# TXmdl_1.net
KiCad netlist of a schematic drawn in Altium Designer
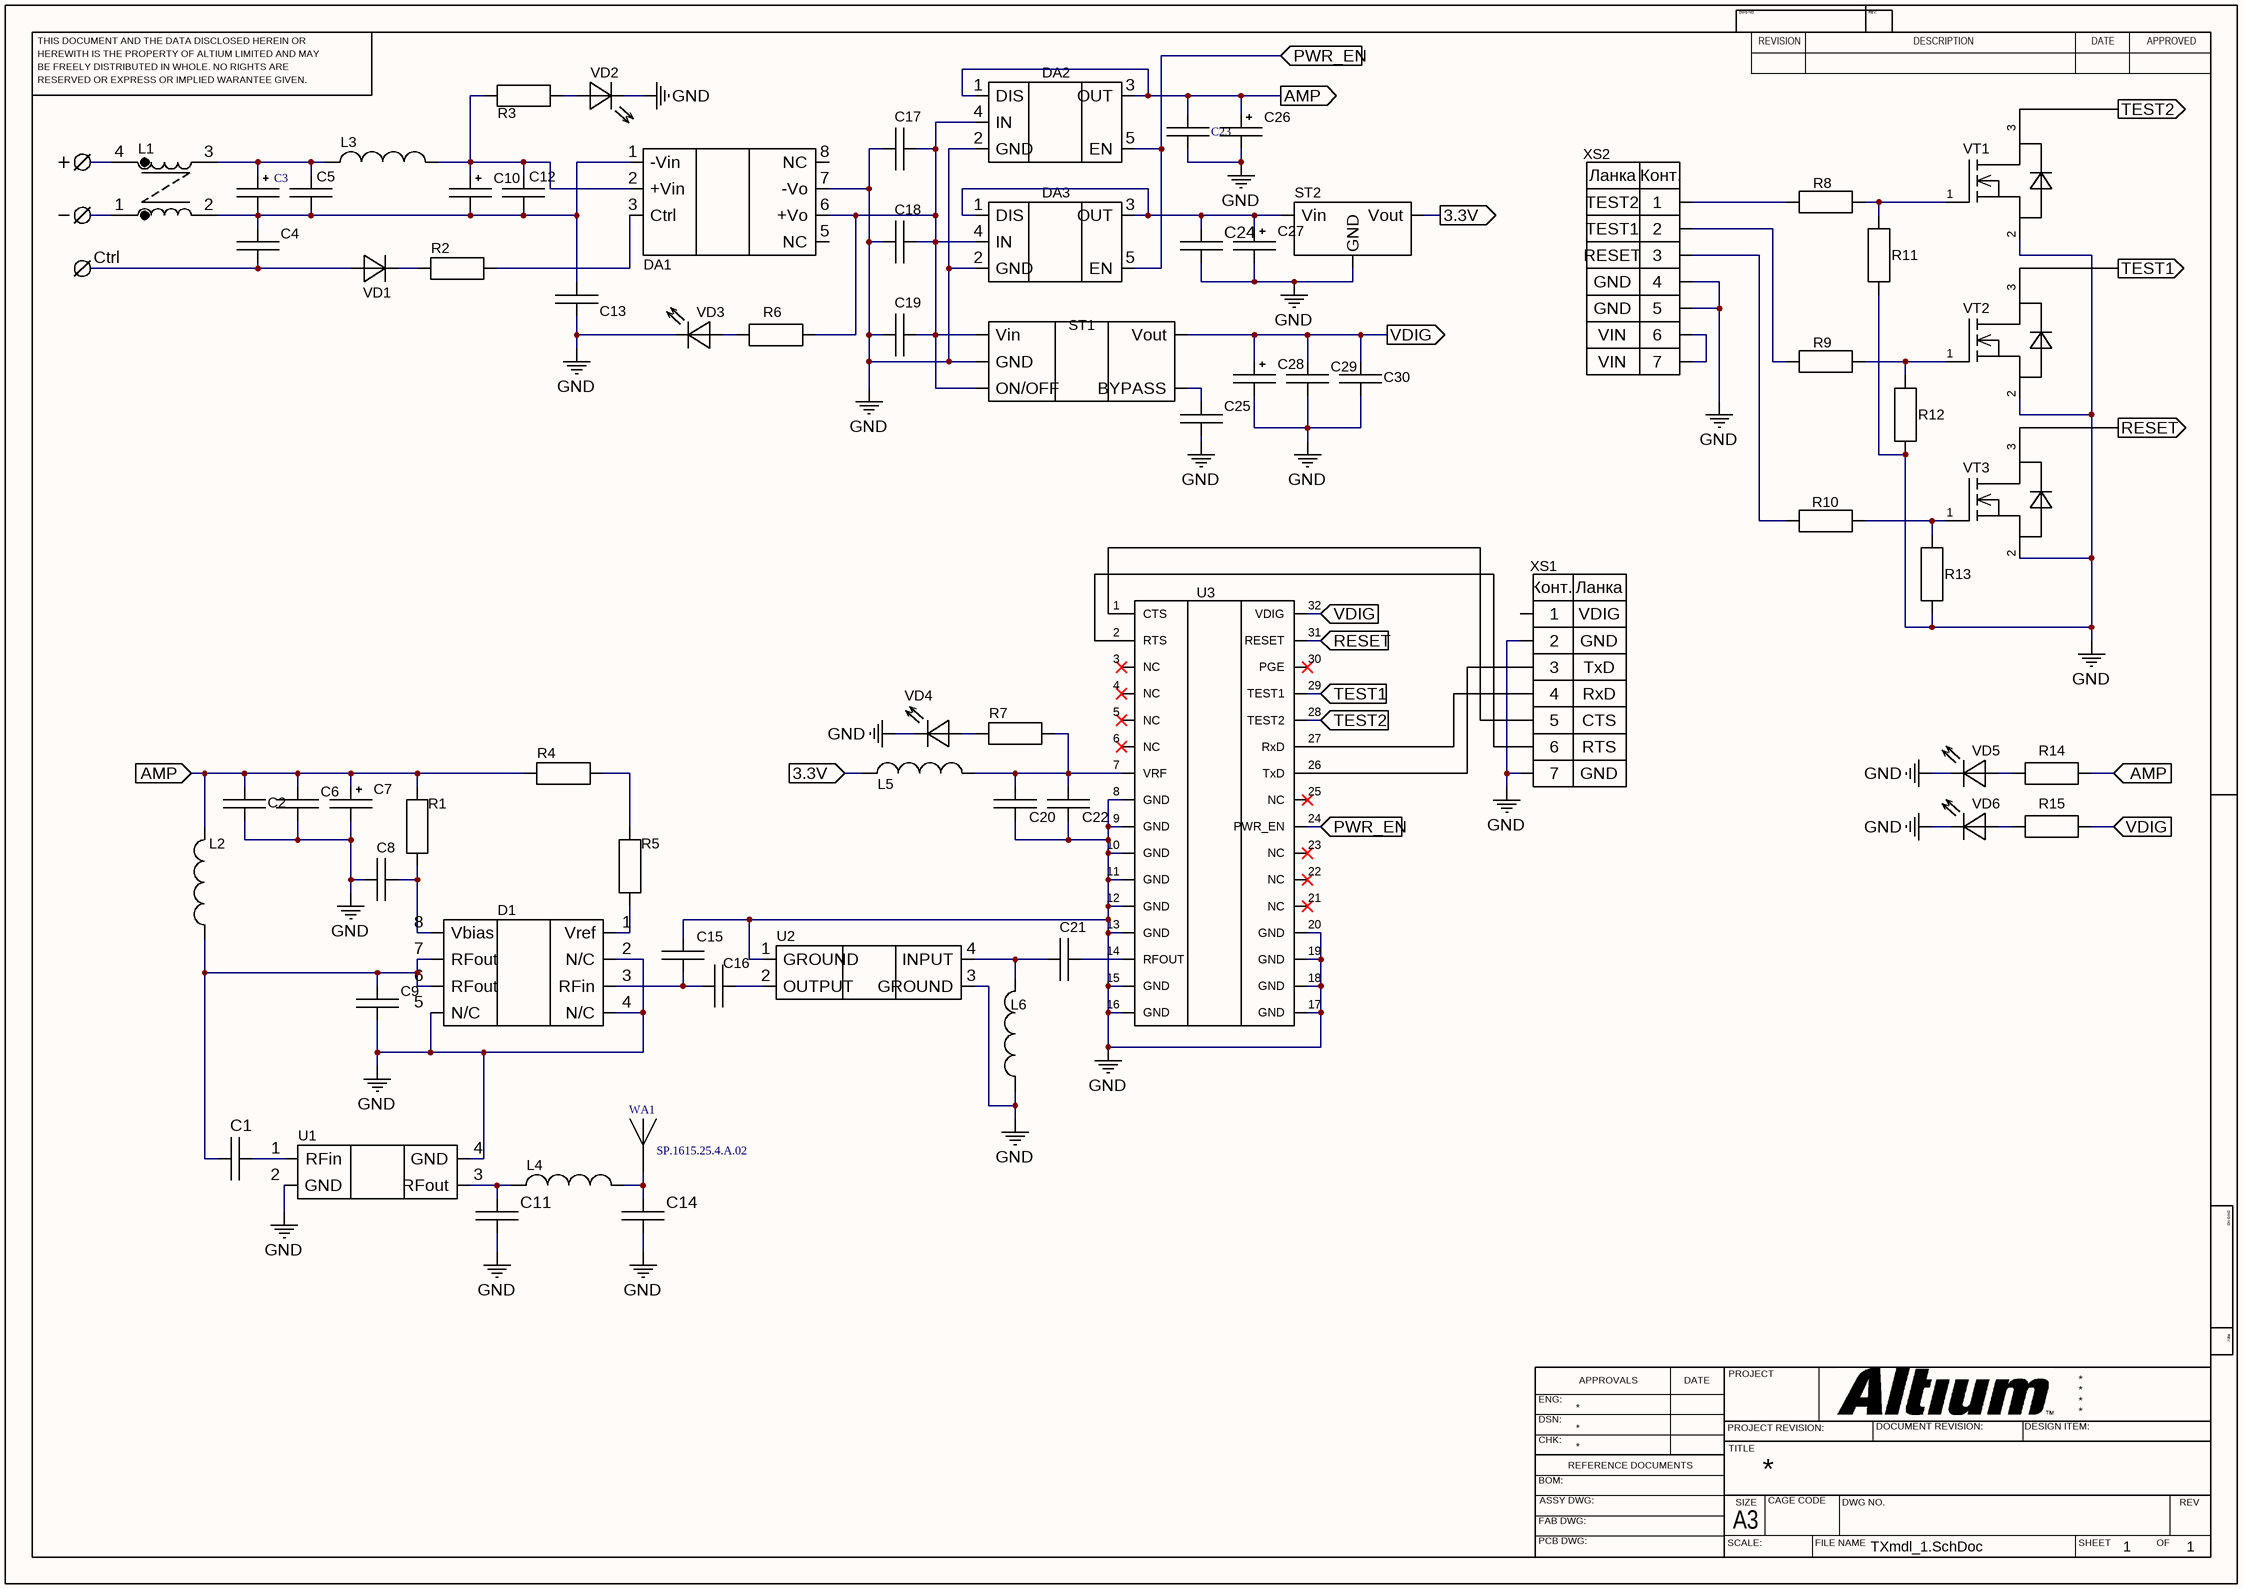
[diagram p0: TXmdl_1.SchDoc]

(export (version "E")
  (design (tool "Eeschema 10.0.6"))
  (components
    (comp (ref "C1")
      (value "Capacitor")
      (footprint "CAP 0603")
      (fields
        (field (name "PART NUMBER") "Capacitor CAP 0603 10 pF")
        (field (name "LIBRARY PART") "Capacitor.schlib")
        (field (name "FOOTPRINT PART") "PcbLibCAP.pcbLib")
      )
      (libsource (lib "DatabaseLib") (part "Capacitor"))
    )
    (comp (ref "C2")
      (value "Capacitor")
      (footprint "CAP 0603")
      (fields
        (field (name "PART NUMBER") "Capacitor CAP 0603 100 pF")
        (field (name "LIBRARY PART") "Capacitor.schlib")
        (field (name "FOOTPRINT PART") "PcbLibCAP.pcbLib")
      )
      (libsource (lib "DatabaseLib") (part "Capacitor"))
    )
    (comp (ref "C3")
      (value "CAP_POL")
      (footprint "CP_Elec_SMD_10x10.5")
      (fields
        (field (name "PART NUMBER") "CAP_POL CP_Elec_SMD_10x10.5 100 uF")
        (field (name "LIBRARY PART") "Capacitor.schlib")
        (field (name "FOOTPRINT PART") "PcbLibCAP.pcbLib")
      )
      (libsource (lib "DatabaseLib") (part "CAP_POL"))
    )
    (comp (ref "C4")
      (value "Capacitor")
      (footprint "CAP 1210")
      (fields
        (field (name "PART NUMBER") "Capacitor CAP 1210 10 uF")
        (field (name "LIBRARY PART") "Capacitor.schlib")
        (field (name "FOOTPRINT PART") "PcbLibCAP.pcbLib")
      )
      (libsource (lib "DatabaseLib") (part "Capacitor"))
    )
    (comp (ref "C5")
      (value "Capacitor")
      (footprint "CAP 1206")
      (fields
        (field (name "PART NUMBER") "Capacitor CAP 1206 10 uF")
        (field (name "LIBRARY PART") "Capacitor.schlib")
        (field (name "FOOTPRINT PART") "PcbLibCAP.pcbLib")
      )
      (libsource (lib "DatabaseLib") (part "Capacitor"))
    )
    (comp (ref "C6")
      (value "Capacitor")
      (footprint "CAP 0603")
      (fields
        (field (name "PART NUMBER") "Capacitor CAP 0603 100 pF")
        (field (name "LIBRARY PART") "Capacitor.schlib")
        (field (name "FOOTPRINT PART") "PcbLibCAP.pcbLib")
      )
      (libsource (lib "DatabaseLib") (part "Capacitor"))
    )
    (comp (ref "C7")
      (value "CAP_POL")
      (footprint "TANTAL_C")
      (fields
        (field (name "PART NUMBER") "CAP_POL TANTAL_C 47 uF")
        (field (name "LIBRARY PART") "Capacitor.schlib")
        (field (name "FOOTPRINT PART") "PcbLibCAP.pcbLib")
      )
      (libsource (lib "DatabaseLib") (part "CAP_POL"))
    )
    (comp (ref "C8")
      (value "Capacitor")
      (footprint "CAP 0603")
      (fields
        (field (name "PART NUMBER") "Capacitor CAP 0603 10 pF")
        (field (name "LIBRARY PART") "Capacitor.schlib")
        (field (name "FOOTPRINT PART") "PcbLibCAP.pcbLib")
      )
      (libsource (lib "DatabaseLib") (part "Capacitor"))
    )
    (comp (ref "C9")
      (value "Capacitor")
      (footprint "CAP 0603")
      (fields
        (field (name "PART NUMBER") "Capacitor CAP 0603 100 pF")
        (field (name "LIBRARY PART") "Capacitor.schlib")
        (field (name "FOOTPRINT PART") "PcbLibCAP.pcbLib")
      )
      (libsource (lib "DatabaseLib") (part "Capacitor"))
    )
    (comp (ref "C10")
      (value "CAP_POL")
      (footprint "CP_Elec_SMD_10x10.5")
      (fields
        (field (name "PART NUMBER") "CAP_POL CP_Elec_SMD_10x10.5 100 uF")
        (field (name "LIBRARY PART") "Capacitor.schlib")
        (field (name "FOOTPRINT PART") "PcbLibCAP.pcbLib")
      )
      (libsource (lib "DatabaseLib") (part "CAP_POL"))
    )
    (comp (ref "C11")
      (value "Capacitor")
      (footprint "CAP 0402")
      (fields
        (field (name "PART NUMBER") "Capacitor CAP 0402 1 pF")
        (field (name "LIBRARY PART") "Capacitor.schlib")
        (field (name "FOOTPRINT PART") "PcbLibCAP.pcbLib")
      )
      (libsource (lib "DatabaseLib") (part "Capacitor"))
    )
    (comp (ref "C12")
      (value "Capacitor")
      (footprint "CAP 1206")
      (fields
        (field (name "PART NUMBER") "Capacitor CAP 1206 10 uF")
        (field (name "LIBRARY PART") "Capacitor.schlib")
        (field (name "FOOTPRINT PART") "PcbLibCAP.pcbLib")
      )
      (libsource (lib "DatabaseLib") (part "Capacitor"))
    )
    (comp (ref "C13")
      (value "Capacitor")
      (footprint "CAP 1206")
      (fields
        (field (name "PART NUMBER") "Capacitor CAP 1206 10 uF")
        (field (name "LIBRARY PART") "Capacitor.schlib")
        (field (name "FOOTPRINT PART") "PcbLibCAP.pcbLib")
      )
      (libsource (lib "DatabaseLib") (part "Capacitor"))
    )
    (comp (ref "C14")
      (value "Capacitor")
      (footprint "CAP 0402")
      (fields
        (field (name "PART NUMBER") "Capacitor CAP 0402 1 pF")
        (field (name "LIBRARY PART") "Capacitor.schlib")
        (field (name "FOOTPRINT PART") "PcbLibCAP.pcbLib")
      )
      (libsource (lib "DatabaseLib") (part "Capacitor"))
    )
    (comp (ref "C15")
      (value "Capacitor")
      (footprint "CAP 0603")
      (fields
        (field (name "PART NUMBER") "Capacitor CAP 0603 10 pF")
        (field (name "LIBRARY PART") "Capacitor.schlib")
        (field (name "FOOTPRINT PART") "PcbLibCAP.pcbLib")
      )
      (libsource (lib "DatabaseLib") (part "Capacitor"))
    )
    (comp (ref "C16")
      (value "Capacitor")
      (footprint "CAP 0402")
      (fields
        (field (name "PART NUMBER") "Capacitor CAP 0402 1 pF")
        (field (name "LIBRARY PART") "Capacitor.schlib")
        (field (name "FOOTPRINT PART") "PcbLibCAP.pcbLib")
      )
      (libsource (lib "DatabaseLib") (part "Capacitor"))
    )
    (comp (ref "C17")
      (value "Capacitor")
      (footprint "CAP 0603")
      (fields
        (field (name "PART NUMBER") "Capacitor CAP 0603 1 uF")
        (field (name "LIBRARY PART") "Capacitor.schlib")
        (field (name "FOOTPRINT PART") "PcbLibCAP.pcbLib")
      )
      (libsource (lib "DatabaseLib") (part "Capacitor"))
    )
    (comp (ref "C18")
      (value "Capacitor")
      (footprint "CAP 0603")
      (fields
        (field (name "PART NUMBER") "Capacitor CAP 0603 1 uF")
        (field (name "LIBRARY PART") "Capacitor.schlib")
        (field (name "FOOTPRINT PART") "PcbLibCAP.pcbLib")
      )
      (libsource (lib "DatabaseLib") (part "Capacitor"))
    )
    (comp (ref "C19")
      (value "Capacitor")
      (footprint "CAP 0603")
      (fields
        (field (name "PART NUMBER") "Capacitor CAP 0603 1 uF")
        (field (name "LIBRARY PART") "Capacitor.schlib")
        (field (name "FOOTPRINT PART") "PcbLibCAP.pcbLib")
      )
      (libsource (lib "DatabaseLib") (part "Capacitor"))
    )
    (comp (ref "C20")
      (value "Capacitor")
      (footprint "CAP 0603")
      (fields
        (field (name "PART NUMBER") "Capacitor CAP 0603 10 pF")
        (field (name "LIBRARY PART") "Capacitor.schlib")
        (field (name "FOOTPRINT PART") "PcbLibCAP.pcbLib")
      )
      (libsource (lib "DatabaseLib") (part "Capacitor"))
    )
    (comp (ref "C21")
      (value "Capacitor")
      (footprint "CAP 0402")
      (fields
        (field (name "PART NUMBER") "Capacitor CAP 0402 1 pF")
        (field (name "LIBRARY PART") "Capacitor.schlib")
        (field (name "FOOTPRINT PART") "PcbLibCAP.pcbLib")
      )
      (libsource (lib "DatabaseLib") (part "Capacitor"))
    )
    (comp (ref "C22")
      (value "Capacitor")
      (footprint "CAP 0402")
      (fields
        (field (name "PART NUMBER") "Capacitor CAP 0402 0.1 uF")
        (field (name "LIBRARY PART") "Capacitor.schlib")
        (field (name "FOOTPRINT PART") "PcbLibCAP.pcbLib")
      )
      (libsource (lib "DatabaseLib") (part "Capacitor"))
    )
    (comp (ref "C23")
      (value "Capacitor")
      (footprint "CAP 0603")
      (fields
        (field (name "PART NUMBER") "Capacitor CAP 0603 0.1 uF")
        (field (name "LIBRARY PART") "Capacitor.schlib")
        (field (name "FOOTPRINT PART") "PcbLibCAP.pcbLib")
      )
      (libsource (lib "DatabaseLib") (part "Capacitor"))
    )
    (comp (ref "C24")
      (value "Capacitor")
      (footprint "CAP 0603")
      (fields
        (field (name "PART NUMBER") "Capacitor CAP 0603 0.1 uF")
        (field (name "LIBRARY PART") "Capacitor.schlib")
        (field (name "FOOTPRINT PART") "PcbLibCAP.pcbLib")
      )
      (libsource (lib "DatabaseLib") (part "Capacitor"))
    )
    (comp (ref "C25")
      (value "Capacitor")
      (footprint "CAP 0603")
      (fields
        (field (name "PART NUMBER") "Capacitor CAP 0603 10 pF")
        (field (name "LIBRARY PART") "Capacitor.schlib")
        (field (name "FOOTPRINT PART") "PcbLibCAP.pcbLib")
      )
      (libsource (lib "DatabaseLib") (part "Capacitor"))
    )
    (comp (ref "C26")
      (value "CAP_POL")
      (footprint "TANTAL_C")
      (fields
        (field (name "PART NUMBER") "CAP_POL TANTAL_C 10 uF")
        (field (name "LIBRARY PART") "Capacitor.schlib")
        (field (name "FOOTPRINT PART") "PcbLibCAP.pcbLib")
      )
      (libsource (lib "DatabaseLib") (part "CAP_POL"))
    )
    (comp (ref "C27")
      (value "CAP_POL")
      (footprint "TANTAL_B")
      (libsource (lib "DatabaseLib") (part "CAP_POL"))
    )
    (comp (ref "C28")
      (value "CAP_POL")
      (footprint "TANTAL_A")
      (libsource (lib "DatabaseLib") (part "CAP_POL"))
    )
    (comp (ref "C29")
      (value "Capacitor")
      (footprint "CAP 0603")
      (fields
        (field (name "PART NUMBER") "Capacitor CAP 0603 10 pF")
        (field (name "LIBRARY PART") "Capacitor.schlib")
        (field (name "FOOTPRINT PART") "PcbLibCAP.pcbLib")
      )
      (libsource (lib "DatabaseLib") (part "Capacitor"))
    )
    (comp (ref "C30")
      (value "Capacitor")
      (footprint "CAP 0603")
      (fields
        (field (name "PART NUMBER") "Capacitor CAP 0603 10 pF")
        (field (name "LIBRARY PART") "Capacitor.schlib")
        (field (name "FOOTPRINT PART") "PcbLibCAP.pcbLib")
      )
      (libsource (lib "DatabaseLib") (part "Capacitor"))
    )
    (comp (ref "D1")
      (value "AH312-S8G")
      (footprint "SOIC-8")
      (fields
        (field (name "PART NUMBER") "AH312-S8G SOIC-8")
        (field (name "LIBRARY PART") "Amplifier.schlib")
        (field (name "FOOTPRINT PART") "PcbLibAMP.pcbLib")
      )
      (libsource (lib "DatabaseLib") (part "AH312-S8G"))
    )
    (comp (ref "DA1")
      (value "URB4805S_10WR3")
      (footprint "URB(A)_S-10WR3")
      (description "Hi-Link\r\nIN: 18-75VDC\r\nOUT: 5VDC/2000mA\r\nPower: 10 W")
      (fields
        (field (name "LIBRARY PART") "DC_DC_Converter.schlib")
        (field (name "FOOTPRINT PART") "PcbLibDC_DC.pcbLib")
      )
      (libsource (lib "DatabaseLib") (part "URB4805S_10WR3"))
    )
    (comp (ref "DA2")
      (value "AP2280")
      (footprint "SOT25")
      (fields
        (field (name "PART NUMBER") "AP2280 SOT25")
        (field (name "LIBRARY PART") "LoadSwitch.schLib")
        (field (name "FOOTPRINT PART") "PcbLibLSW.pcbLib")
      )
      (libsource (lib "DatabaseLib") (part "AP2280"))
    )
    (comp (ref "DA3")
      (value "AP2280")
      (footprint "SOT25")
      (fields
        (field (name "PART NUMBER") "AP2280 SOT25")
        (field (name "LIBRARY PART") "LoadSwitch.schLib")
        (field (name "FOOTPRINT PART") "PcbLibLSW.pcbLib")
      )
      (libsource (lib "DatabaseLib") (part "AP2280"))
    )
    (comp (ref "L1")
      (value "Toroidal_Chokes")
      (footprint "XFMR_HCTC-4-1.7")
      (libsource (lib "DatabaseLib") (part "Toroidal_Chokes"))
    )
    (comp (ref "L2")
      (value "Inductance")
      (footprint "L 0603")
      (fields
        (field (name "PART NUMBER") "Inductance L 0603 39 nH")
        (field (name "LIBRARY PART") "Inductance.schlib")
        (field (name "FOOTPRINT PART") "PcbLibL.pcbLib")
      )
      (libsource (lib "DatabaseLib") (part "Inductance"))
    )
    (comp (ref "L3")
      (value "Inductance")
      (footprint "SSB0503")
      (fields
        (field (name "PART NUMBER") "Inductance SSB0503 15 uH")
        (field (name "LIBRARY PART") "Inductance.schlib")
        (field (name "FOOTPRINT PART") "PcbLibL.pcbLib")
      )
      (libsource (lib "DatabaseLib") (part "Inductance"))
    )
    (comp (ref "L4")
      (value "Inductance")
      (footprint "L 0603")
      (fields
        (field (name "PART NUMBER") "Inductance L 0603 39 nH")
        (field (name "LIBRARY PART") "Inductance.schlib")
        (field (name "FOOTPRINT PART") "PcbLibL.pcbLib")
      )
      (libsource (lib "DatabaseLib") (part "Inductance"))
    )
    (comp (ref "L5")
      (value "Ferrite_Bead")
      (footprint "L 0805")
      (fields
        (field (name "PART NUMBER") "Ferrite_Bead L 0805 220 Om")
        (field (name "LIBRARY PART") "Inductance.schlib")
        (field (name "FOOTPRINT PART") "PcbLibL.pcbLib")
      )
      (libsource (lib "DatabaseLib") (part "Ferrite_Bead"))
    )
    (comp (ref "L6")
      (value "Inductance")
      (footprint "L 0603")
      (fields
        (field (name "PART NUMBER") "Inductance L 0603 39 nH")
        (field (name "LIBRARY PART") "Inductance.schlib")
        (field (name "FOOTPRINT PART") "PcbLibL.pcbLib")
      )
      (libsource (lib "DatabaseLib") (part "Inductance"))
    )
    (comp (ref "R1")
      (value "Resistor")
      (footprint "RES 0603")
      (fields
        (field (name "PART NUMBER") "Resistor RES 0603 0 Om")
        (field (name "LIBRARY PART") "Resistor.schlib")
        (field (name "FOOTPRINT PART") "PcbLibRES.pcbLib")
      )
      (libsource (lib "DatabaseLib") (part "Resistor"))
    )
    (comp (ref "R2")
      (value "Resistor")
      (footprint "RES 0603")
      (fields
        (field (name "PART NUMBER") "Resistor RES 0603 100 Om")
        (field (name "LIBRARY PART") "Resistor.schlib")
        (field (name "FOOTPRINT PART") "PcbLibRES.pcbLib")
      )
      (libsource (lib "") (part "Resistor_2"))
    )
    (comp (ref "R3")
      (value "Resistor")
      (footprint "RES 0603")
      (fields
        (field (name "PART NUMBER") "Resistor RES 0603 4.7 kOm")
        (field (name "LIBRARY PART") "Resistor.schlib")
        (field (name "FOOTPRINT PART") "PcbLibRES.pcbLib")
      )
      (libsource (lib "") (part "Resistor_2"))
    )
    (comp (ref "R4")
      (value "Resistor")
      (footprint "RES 0603")
      (fields
        (field (name "PART NUMBER") "Resistor RES 0603 0 Om")
        (field (name "LIBRARY PART") "Resistor.schlib")
        (field (name "FOOTPRINT PART") "PcbLibRES.pcbLib")
      )
      (libsource (lib "") (part "Resistor_2"))
    )
    (comp (ref "R5")
      (value "Resistor")
      (footprint "RES 0603")
      (fields
        (field (name "PART NUMBER") "Resistor RES 0603 0 Om")
        (field (name "LIBRARY PART") "Resistor.schlib")
        (field (name "FOOTPRINT PART") "PcbLibRES.pcbLib")
      )
      (libsource (lib "DatabaseLib") (part "Resistor"))
    )
    (comp (ref "R6")
      (value "Resistor")
      (footprint "RES 0603")
      (fields
        (field (name "PART NUMBER") "Resistor RES 0603 4.7 kOm")
        (field (name "LIBRARY PART") "Resistor.schlib")
        (field (name "FOOTPRINT PART") "PcbLibRES.pcbLib")
      )
      (libsource (lib "") (part "Resistor_1"))
    )
    (comp (ref "R7")
      (value "Resistor")
      (footprint "RES 0603")
      (fields
        (field (name "PART NUMBER") "Resistor RES 0603 4.7 kOm")
        (field (name "LIBRARY PART") "Resistor.schlib")
        (field (name "FOOTPRINT PART") "PcbLibRES.pcbLib")
      )
      (libsource (lib "") (part "Resistor_1"))
    )
    (comp (ref "R8")
      (value "Resistor")
      (footprint "RES 0603")
      (fields
        (field (name "PART NUMBER") "Resistor RES 0603 1 Om")
        (field (name "LIBRARY PART") "Resistor.schlib")
        (field (name "FOOTPRINT PART") "PcbLibRES.pcbLib")
      )
      (libsource (lib "") (part "Resistor_1"))
    )
    (comp (ref "R9")
      (value "Resistor")
      (footprint "RES 0603")
      (fields
        (field (name "PART NUMBER") "Resistor RES 0603 1 Om")
        (field (name "LIBRARY PART") "Resistor.schlib")
        (field (name "FOOTPRINT PART") "PcbLibRES.pcbLib")
      )
      (libsource (lib "") (part "Resistor_1"))
    )
    (comp (ref "R10")
      (value "Resistor")
      (footprint "RES 0603")
      (fields
        (field (name "PART NUMBER") "Resistor RES 0603 1 Om")
        (field (name "LIBRARY PART") "Resistor.schlib")
        (field (name "FOOTPRINT PART") "PcbLibRES.pcbLib")
      )
      (libsource (lib "") (part "Resistor_1"))
    )
    (comp (ref "R11")
      (value "Resistor")
      (footprint "RES 0603")
      (fields
        (field (name "PART NUMBER") "Resistor RES 0603 1 Om")
        (field (name "LIBRARY PART") "Resistor.schlib")
        (field (name "FOOTPRINT PART") "PcbLibRES.pcbLib")
      )
      (libsource (lib "DatabaseLib") (part "Resistor"))
    )
    (comp (ref "R12")
      (value "Resistor")
      (footprint "RES 0603")
      (fields
        (field (name "PART NUMBER") "Resistor RES 0603 1 Om")
        (field (name "LIBRARY PART") "Resistor.schlib")
        (field (name "FOOTPRINT PART") "PcbLibRES.pcbLib")
      )
      (libsource (lib "DatabaseLib") (part "Resistor"))
    )
    (comp (ref "R13")
      (value "Resistor")
      (footprint "RES 0603")
      (fields
        (field (name "PART NUMBER") "Resistor RES 0603 1 Om")
        (field (name "LIBRARY PART") "Resistor.schlib")
        (field (name "FOOTPRINT PART") "PcbLibRES.pcbLib")
      )
      (libsource (lib "DatabaseLib") (part "Resistor"))
    )
    (comp (ref "R14")
      (value "Resistor")
      (footprint "RES 0603")
      (fields
        (field (name "PART NUMBER") "Resistor RES 0603 4.7 kOm")
        (field (name "LIBRARY PART") "Resistor.schlib")
        (field (name "FOOTPRINT PART") "PcbLibRES.pcbLib")
      )
      (libsource (lib "") (part "Resistor_1"))
    )
    (comp (ref "R15")
      (value "Resistor")
      (footprint "RES 0603")
      (fields
        (field (name "PART NUMBER") "Resistor RES 0603 4.7 kOm")
        (field (name "LIBRARY PART") "Resistor.schlib")
        (field (name "FOOTPRINT PART") "PcbLibRES.pcbLib")
      )
      (libsource (lib "") (part "Resistor_1"))
    )
    (comp (ref "ST1")
      (value "LP2985-33")
      (footprint "SOT-23_1.45")
      (fields
        (field (name "PART NUMBER") "LP2985-33 SOT-23_1.45")
        (field (name "LIBRARY PART") "LDO.schlib")
        (field (name "FOOTPRINT PART") "PcbLibLDO.pcbLib")
      )
      (libsource (lib "DatabaseLib") (part "LP2985-33"))
    )
    (comp (ref "ST2")
      (value "LD1117-33")
      (footprint "DPAK_TO-252")
      (fields
        (field (name "PART NUMBER") "LD1117-33 DPAK_TO-252")
        (field (name "LIBRARY PART") "LDO.schlib")
        (field (name "FOOTPRINT PART") "PcbLibLDO.pcbLib")
      )
      (libsource (lib "DatabaseLib") (part "LD1117-33"))
    )
    (comp (ref "U1")
      (value "BFCN-1860+")
      (footprint "FV1206-4")
      (description "Bandpass Filter\r\n1580 to 2200 MHz")
      (fields
        (field (name "PART NUMBER") "BFCN-1860+ FV1206-4")
        (field (name "LIBRARY PART") "Filter.schlib")
      )
      (libsource (lib "DatabaseLib") (part "BFCN-1860+"))
    )
    (comp (ref "U2")
      (value "LAT-2+")
      (footprint "SOT143")
      (description "wideband, DC to 2500 MHz")
      (fields
        (field (name "PART NUMBER") "LAT-2+ SOT143")
        (field (name "LIBRARY PART") "RF_Attenuator.schlib")
      )
      (libsource (lib "DatabaseLib") (part "LAT-2+"))
    )
    (comp (ref "U3")
      (value "STX3_Module")
      (footprint "STX3_TxSTL_32")
      (description "STX3 satellite transmitter")
      (fields
        (field (name "PART NUMBER") "STX3_Module STX3_TxSTL_32")
        (field (name "LIBRARY PART") "TRANSMITTER.schlib")
      )
      (libsource (lib "DatabaseLib") (part "STX3_Module"))
    )
    (comp (ref "VD1")
      (value "1N4148WS")
      (footprint "SOD323")
      (description "High Speed Switching Diode\r\nFeatures\r\n- VR 75V\r\n- IFAV 150mA")
      (fields (field (name "PART NUMBER") "1N4148WS SOD323") (field (name "LIBRARY PART") "Diode.schlib"))
      (libsource (lib "DatabaseLib") (part "1N4148WS"))
    )
    (comp (ref "VD2")
      (value "LED")
      (footprint "LED_SMD_0603")
      (fields
        (field (name "PART NUMBER") "LED_RGB LED_SMD_0603")
        (field (name "LIBRARY PART") "LED.schlib")
        (field (name "FOOTPRINT PART") "PcbLibLED.pcbLib")
      )
      (libsource (lib "DatabaseLib") (part "LED_RGB"))
    )
    (comp (ref "VD3")
      (value "LED")
      (footprint "LED_SMD_0603")
      (fields
        (field (name "PART NUMBER") "LED_RGB LED_SMD_0603")
        (field (name "LIBRARY PART") "LED.schlib")
        (field (name "FOOTPRINT PART") "PcbLibLED.pcbLib")
      )
      (libsource (lib "DatabaseLib") (part "LED_RGB"))
    )
    (comp (ref "VD4")
      (value "LED")
      (footprint "LED_SMD_0603")
      (fields
        (field (name "PART NUMBER") "LED_RGB LED_SMD_0603")
        (field (name "LIBRARY PART") "LED.schlib")
        (field (name "FOOTPRINT PART") "PcbLibLED.pcbLib")
      )
      (libsource (lib "DatabaseLib") (part "LED_RGB"))
    )
    (comp (ref "VD5")
      (value "LED")
      (footprint "LED_SMD_0603")
      (fields
        (field (name "PART NUMBER") "LED_RGB LED_SMD_0603")
        (field (name "LIBRARY PART") "LED.schlib")
        (field (name "FOOTPRINT PART") "PcbLibLED.pcbLib")
      )
      (libsource (lib "DatabaseLib") (part "LED_RGB"))
    )
    (comp (ref "VD6")
      (value "LED")
      (footprint "LED_SMD_0603")
      (fields
        (field (name "PART NUMBER") "LED_RGB LED_SMD_0603")
        (field (name "LIBRARY PART") "LED.schlib")
        (field (name "FOOTPRINT PART") "PcbLibLED.pcbLib")
      )
      (libsource (lib "DatabaseLib") (part "LED_RGB"))
    )
    (comp (ref "VT1")
      (value "2N7002")
      (footprint "SOT-23-3")
      (fields
        (field (name "PART NUMBER") "2N7002 SOT-23-3")
        (field (name "LIBRARY PART") "MOSFET.schlib")
        (field (name "FOOTPRINT PART") "PcbLibMOSFET.pcbLib")
      )
      (libsource (lib "DatabaseLib") (part "2N7002"))
    )
    (comp (ref "VT2")
      (value "2N7002")
      (footprint "SOT-23-3")
      (fields
        (field (name "PART NUMBER") "2N7002 SOT-23-3")
        (field (name "LIBRARY PART") "MOSFET.schlib")
        (field (name "FOOTPRINT PART") "PcbLibMOSFET.pcbLib")
      )
      (libsource (lib "DatabaseLib") (part "2N7002"))
    )
    (comp (ref "VT3")
      (value "2N7002")
      (footprint "SOT-23-3")
      (fields
        (field (name "PART NUMBER") "2N7002 SOT-23-3")
        (field (name "LIBRARY PART") "MOSFET.schlib")
        (field (name "FOOTPRINT PART") "PcbLibMOSFET.pcbLib")
      )
      (libsource (lib "DatabaseLib") (part "2N7002"))
    )
    (comp (ref "WA1")
      (value "SP.1615.25.4.A.02")
      (footprint "A1615_25x25x4")
      (description "25*25*4mm  Globalstar 25mm 1615Mhz")
      (fields
        (field (name "PART NUMBER") "SP.1615.25.4.A.02 A1615_25x25x4")
        (field (name "LIBRARY PART") "Antenna.schlib")
      )
      (libsource (lib "DatabaseLib") (part "SP.1615.25.4.A.02"))
    )
    (comp (ref "XS1")
      (value "WPH-3002-1XX-2GXB-XR")
      (footprint "TSM-107-02-L-SV-A-P")
      (libsource (lib "DatabaseLib") (part "WPH-3002-1XX-2GXB-XR"))
    )
    (comp (ref "XS2")
      (value "WPH-3002-1XX-2GXB-XR")
      (footprint "TSM-107-02-L-SV-A-P")
      (libsource (lib "") (part "WPH-3002-1XX-2GXB-XR_1"))
    )
  )
  (nets
    (net (code "1") (name "/3.3V") (class "Default")
      (node (ref "L5") (pin "1") (pinfunction "1_1") (pintype "passive"))
      (node (ref "ST2") (pin "2") (pinfunction "Vout_2") (pintype "passive"))
    )
    (net (code "2") (name "/AMP") (class "Default")
      (node (ref "C2") (pin "1") (pinfunction "1_1") (pintype "passive"))
      (node (ref "C23") (pin "1") (pinfunction "1_1") (pintype "passive"))
      (node (ref "C26") (pin "1") (pinfunction "1_1") (pintype "passive"))
      (node (ref "C6") (pin "1") (pinfunction "1_1") (pintype "passive"))
      (node (ref "C7") (pin "1") (pinfunction "1_1") (pintype "passive"))
      (node (ref "DA2") (pin "1") (pinfunction "DIS_1") (pintype "passive"))
      (node (ref "DA2") (pin "3") (pinfunction "OUT_3") (pintype "passive"))
      (node (ref "L2") (pin "2") (pinfunction "2_2") (pintype "passive"))
      (node (ref "R1") (pin "2") (pinfunction "2_2") (pintype "passive"))
      (node (ref "R14") (pin "1") (pinfunction "1_1") (pintype "passive"))
      (node (ref "R4") (pin "1") (pinfunction "1_1") (pintype "passive"))
    )
    (net (code "3") (name "/Ctrl") (class "Default")
      (node (ref "C4") (pin "2") (pinfunction "2_2") (pintype "passive"))
      (node (ref "VD1") (pin "2") (pinfunction "2_2") (pintype "passive"))
    )
    (net (code "4") (name "/PWR_EN") (class "Default")
      (node (ref "DA2") (pin "5") (pinfunction "EN_5") (pintype "passive"))
      (node (ref "DA3") (pin "5") (pinfunction "EN_5") (pintype "passive"))
      (node (ref "U3") (pin "24") (pinfunction "PWR_EN_24") (pintype "passive"))
    )
    (net (code "5") (name "/RESET") (class "Default")
      (node (ref "U3") (pin "31") (pinfunction "RESET_31") (pintype "passive"))
      (node (ref "VT3") (pin "3") (pinfunction "D_3") (pintype "passive"))
    )
    (net (code "6") (name "/TEST1") (class "Default")
      (node (ref "U3") (pin "29") (pinfunction "TEST1_29") (pintype "passive"))
      (node (ref "VT2") (pin "3") (pinfunction "D_3") (pintype "passive"))
    )
    (net (code "7") (name "/TEST2") (class "Default")
      (node (ref "U3") (pin "28") (pinfunction "TEST2_28") (pintype "passive"))
      (node (ref "VT1") (pin "3") (pinfunction "D_3") (pintype "passive"))
    )
    (net (code "8") (name "/VDIG") (class "Default")
      (node (ref "C28") (pin "1") (pinfunction "1_1") (pintype "passive"))
      (node (ref "C29") (pin "2") (pinfunction "2_2") (pintype "passive"))
      (node (ref "C30") (pin "2") (pinfunction "2_2") (pintype "passive"))
      (node (ref "R15") (pin "1") (pinfunction "1_1") (pintype "passive"))
      (node (ref "ST1") (pin "5") (pinfunction "Vout_5") (pintype "passive"))
      (node (ref "U3") (pin "32") (pinfunction "VDIG_32") (pintype "passive"))
    )
    (net (code "9") (name "GND") (class "Default")
      (node (ref "C11") (pin "2") (pinfunction "2_2") (pintype "passive"))
      (node (ref "C13") (pin "2") (pinfunction "2_2") (pintype "passive"))
      (node (ref "C14") (pin "2") (pinfunction "2_2") (pintype "passive"))
      (node (ref "C15") (pin "1") (pinfunction "1_1") (pintype "passive"))
      (node (ref "C17") (pin "2") (pinfunction "2_2") (pintype "passive"))
      (node (ref "C18") (pin "2") (pinfunction "2_2") (pintype "passive"))
      (node (ref "C19") (pin "1") (pinfunction "1_1") (pintype "passive"))
      (node (ref "C2") (pin "2") (pinfunction "2_2") (pintype "passive"))
      (node (ref "C20") (pin "2") (pinfunction "2_2") (pintype "passive"))
      (node (ref "C22") (pin "1") (pinfunction "1_1") (pintype "passive"))
      (node (ref "C23") (pin "2") (pinfunction "2_2") (pintype "passive"))
      (node (ref "C24") (pin "2") (pinfunction "2_2") (pintype "passive"))
      (node (ref "C25") (pin "1") (pinfunction "1_1") (pintype "passive"))
      (node (ref "C26") (pin "2") (pinfunction "2_2") (pintype "passive"))
      (node (ref "C27") (pin "2") (pinfunction "2_2") (pintype "passive"))
      (node (ref "C28") (pin "2") (pinfunction "2_2") (pintype "passive"))
      (node (ref "C29") (pin "1") (pinfunction "1_1") (pintype "passive"))
      (node (ref "C30") (pin "1") (pinfunction "1_1") (pintype "passive"))
      (node (ref "C6") (pin "2") (pinfunction "2_2") (pintype "passive"))
      (node (ref "C7") (pin "2") (pinfunction "2_2") (pintype "passive"))
      (node (ref "C8") (pin "1") (pinfunction "1_1") (pintype "passive"))
      (node (ref "C9") (pin "2") (pinfunction "2_2") (pintype "passive"))
      (node (ref "D1") (pin "2") (pinfunction "N/C_2") (pintype "passive"))
      (node (ref "D1") (pin "4") (pinfunction "N/C_4") (pintype "passive"))
      (node (ref "D1") (pin "5") (pinfunction "N/C_5") (pintype "passive"))
      (node (ref "DA1") (pin "7") (pinfunction "-Vo_7") (pintype "passive"))
      (node (ref "DA2") (pin "2") (pinfunction "GND_2") (pintype "passive"))
      (node (ref "DA3") (pin "2") (pinfunction "GND_2") (pintype "passive"))
      (node (ref "L6") (pin "1") (pinfunction "1_1") (pintype "passive"))
      (node (ref "R11") (pin "1") (pinfunction "1_1") (pintype "passive"))
      (node (ref "R12") (pin "1") (pinfunction "1_1") (pintype "passive"))
      (node (ref "R13") (pin "1") (pinfunction "1_1") (pintype "passive"))
      (node (ref "ST1") (pin "2") (pinfunction "GND_2") (pintype "passive"))
      (node (ref "ST2") (pin "1") (pinfunction "GND_1") (pintype "passive"))
      (node (ref "U1") (pin "2") (pinfunction "GND_2") (pintype "passive"))
      (node (ref "U1") (pin "4") (pinfunction "GND_4") (pintype "passive"))
      (node (ref "U2") (pin "1") (pinfunction "GROUND_1") (pintype "power_in"))
      (node (ref "U2") (pin "3") (pinfunction "GROUND_3") (pintype "power_in"))
      (node (ref "U3") (pin "10") (pinfunction "GND_10") (pintype "passive"))
      (node (ref "U3") (pin "11") (pinfunction "GND_11") (pintype "passive"))
      (node (ref "U3") (pin "12") (pinfunction "GND_12") (pintype "passive"))
      (node (ref "U3") (pin "13") (pinfunction "GND_13") (pintype "passive"))
      (node (ref "U3") (pin "15") (pinfunction "GND_15") (pintype "passive"))
      (node (ref "U3") (pin "16") (pinfunction "GND_16") (pintype "passive"))
      (node (ref "U3") (pin "17") (pinfunction "GND_17") (pintype "passive"))
      (node (ref "U3") (pin "18") (pinfunction "GND_18") (pintype "passive"))
      (node (ref "U3") (pin "19") (pinfunction "GND_19") (pintype "passive"))
      (node (ref "U3") (pin "20") (pinfunction "GND_20") (pintype "passive"))
      (node (ref "U3") (pin "8") (pinfunction "GND_8") (pintype "passive"))
      (node (ref "U3") (pin "9") (pinfunction "GND_9") (pintype "passive"))
      (node (ref "VD2") (pin "2") (pinfunction "2_2") (pintype "passive"))
      (node (ref "VD3") (pin "2") (pinfunction "2_2") (pintype "passive"))
      (node (ref "VD4") (pin "2") (pinfunction "2_2") (pintype "passive"))
      (node (ref "VD5") (pin "2") (pinfunction "2_2") (pintype "passive"))
      (node (ref "VD6") (pin "2") (pinfunction "2_2") (pintype "passive"))
      (node (ref "VT1") (pin "2") (pinfunction "S_2") (pintype "passive"))
      (node (ref "VT2") (pin "2") (pinfunction "S_2") (pintype "passive"))
      (node (ref "VT3") (pin "2") (pinfunction "S_2") (pintype "passive"))
      (node (ref "XS1") (pin "2") (pinfunction "2_2") (pintype "passive"))
      (node (ref "XS1") (pin "7") (pinfunction "7_7") (pintype "passive"))
      (node (ref "XS2") (pin "4") (pinfunction "4_4") (pintype "passive"))
      (node (ref "XS2") (pin "5") (pinfunction "5_5") (pintype "passive"))
    )
    (net (code "10") (name "Net-(C1-Pad1)") (class "Default")
      (node (ref "C1") (pin "1") (pinfunction "1_1") (pintype "passive"))
      (node (ref "C9") (pin "1") (pinfunction "1_1") (pintype "passive"))
      (node (ref "D1") (pin "6") (pinfunction "RFout_6") (pintype "passive"))
      (node (ref "D1") (pin "7") (pinfunction "RFout_7") (pintype "passive"))
      (node (ref "L2") (pin "1") (pinfunction "1_1") (pintype "passive"))
    )
    (net (code "11") (name "Net-(C3-Pad1)") (class "Default")
      (node (ref "C3") (pin "1") (pinfunction "1_1") (pintype "passive"))
      (node (ref "C5") (pin "2") (pinfunction "2_2") (pintype "passive"))
      (node (ref "L1") (pin "3") (pinfunction "3_3") (pintype "passive"))
      (node (ref "L3") (pin "1") (pinfunction "1_1") (pintype "passive"))
    )
    (net (code "12") (name "Net-(C14-Pad1)") (class "Default")
      (node (ref "C14") (pin "1") (pinfunction "1_1") (pintype "passive"))
      (node (ref "L4") (pin "2") (pinfunction "2_2") (pintype "passive"))
      (node (ref "WA1") (pin "1") (pinfunction "1_1") (pintype "passive"))
    )
    (net (code "13") (name "Net-(D1-RFin)") (class "Default")
      (node (ref "C15") (pin "2") (pinfunction "2_2") (pintype "passive"))
      (node (ref "C16") (pin "1") (pinfunction "1_1") (pintype "passive"))
      (node (ref "D1") (pin "3") (pinfunction "RFin_3") (pintype "passive"))
    )
    (net (code "14") (name "Net-(D1-Vbias)") (class "Default")
      (node (ref "C8") (pin "2") (pinfunction "2_2") (pintype "passive"))
      (node (ref "D1") (pin "8") (pinfunction "Vbias_8") (pintype "passive"))
      (node (ref "R1") (pin "1") (pinfunction "1_1") (pintype "passive"))
    )
    (net (code "15") (name "Net-(D1-Vref)") (class "Default")
      (node (ref "D1") (pin "1") (pinfunction "Vref_1") (pintype "passive"))
      (node (ref "R5") (pin "1") (pinfunction "1_1") (pintype "passive"))
    )
    (net (code "16") (name "Net-(DA1-+Vin)") (class "Default")
      (node (ref "C10") (pin "1") (pinfunction "1_1") (pintype "passive"))
      (node (ref "C12") (pin "2") (pinfunction "2_2") (pintype "passive"))
      (node (ref "DA1") (pin "2") (pinfunction "+Vin_2") (pintype "passive"))
      (node (ref "L3") (pin "2") (pinfunction "2_2") (pintype "passive"))
      (node (ref "R3") (pin "1") (pinfunction "1_1") (pintype "passive"))
    )
    (net (code "17") (name "Net-(DA1-+Vo)") (class "Default")
      (node (ref "C17") (pin "1") (pinfunction "1_1") (pintype "passive"))
      (node (ref "C18") (pin "1") (pinfunction "1_1") (pintype "passive"))
      (node (ref "C19") (pin "2") (pinfunction "2_2") (pintype "passive"))
      (node (ref "DA1") (pin "6") (pinfunction "+Vo_6") (pintype "passive"))
      (node (ref "DA2") (pin "4") (pinfunction "IN_4") (pintype "passive"))
      (node (ref "DA3") (pin "4") (pinfunction "IN_4") (pintype "passive"))
      (node (ref "R6") (pin "1") (pinfunction "1_1") (pintype "passive"))
      (node (ref "ST1") (pin "1") (pinfunction "Vin_1") (pintype "passive"))
      (node (ref "ST1") (pin "3") (pinfunction "ON/OFF_3") (pintype "passive"))
    )
    (net (code "18") (name "Net-(DA1--Vin)") (class "Default")
      (node (ref "C10") (pin "2") (pinfunction "2_2") (pintype "passive"))
      (node (ref "C12") (pin "1") (pinfunction "1_1") (pintype "passive"))
      (node (ref "C13") (pin "1") (pinfunction "1_1") (pintype "passive"))
      (node (ref "C3") (pin "2") (pinfunction "2_2") (pintype "passive"))
      (node (ref "C4") (pin "1") (pinfunction "1_1") (pintype "passive"))
      (node (ref "C5") (pin "1") (pinfunction "1_1") (pintype "passive"))
      (node (ref "DA1") (pin "1") (pinfunction "-Vin_1") (pintype "passive"))
      (node (ref "L1") (pin "2") (pinfunction "2_2") (pintype "passive"))
    )
    (net (code "19") (name "Net-(DA1-Ctrl)") (class "Default")
      (node (ref "DA1") (pin "3") (pinfunction "Ctrl_3") (pintype "passive"))
      (node (ref "R2") (pin "2") (pinfunction "2_2") (pintype "passive"))
    )
    (net (code "20") (name "Net-(DA3-DIS)") (class "Default")
      (node (ref "C24") (pin "1") (pinfunction "1_1") (pintype "passive"))
      (node (ref "C27") (pin "1") (pinfunction "1_1") (pintype "passive"))
      (node (ref "DA3") (pin "1") (pinfunction "DIS_1") (pintype "passive"))
      (node (ref "DA3") (pin "3") (pinfunction "OUT_3") (pintype "passive"))
      (node (ref "ST2") (pin "3") (pinfunction "Vin_3") (pintype "passive"))
    )
    (net (code "21") (name "Net-(R2-Pad1)") (class "Default")
      (node (ref "R2") (pin "1") (pinfunction "1_1") (pintype "passive"))
      (node (ref "VD1") (pin "1") (pinfunction "1_1") (pintype "passive"))
    )
    (net (code "22") (name "Net-(R3-Pad2)") (class "Default")
      (node (ref "R3") (pin "2") (pinfunction "2_2") (pintype "passive"))
      (node (ref "VD2") (pin "1") (pinfunction "1_1") (pintype "passive"))
    )
    (net (code "23") (name "Net-(R4-Pad2)") (class "Default")
      (node (ref "R4") (pin "2") (pinfunction "2_2") (pintype "passive"))
      (node (ref "R5") (pin "2") (pinfunction "2_2") (pintype "passive"))
    )
    (net (code "24") (name "Net-(R6-Pad2)") (class "Default")
      (node (ref "R6") (pin "2") (pinfunction "2_2") (pintype "passive"))
      (node (ref "VD3") (pin "1") (pinfunction "1_1") (pintype "passive"))
    )
    (net (code "25") (name "Net-(R7-Pad2)") (class "Default")
      (node (ref "R7") (pin "2") (pinfunction "2_2") (pintype "passive"))
      (node (ref "VD4") (pin "1") (pinfunction "1_1") (pintype "passive"))
    )
    (net (code "26") (name "Net-(R8-Pad2)") (class "Default")
      (node (ref "R8") (pin "2") (pinfunction "2_2") (pintype "passive"))
      (node (ref "XS2") (pin "1") (pinfunction "1_1") (pintype "passive"))
    )
    (net (code "27") (name "Net-(R9-Pad2)") (class "Default")
      (node (ref "R9") (pin "2") (pinfunction "2_2") (pintype "passive"))
      (node (ref "XS2") (pin "2") (pinfunction "2_2") (pintype "passive"))
    )
    (net (code "28") (name "Net-(R10-Pad2)") (class "Default")
      (node (ref "R10") (pin "2") (pinfunction "2_2") (pintype "passive"))
      (node (ref "XS2") (pin "3") (pinfunction "3_3") (pintype "passive"))
    )
    (net (code "29") (name "Net-(R14-Pad2)") (class "Default")
      (node (ref "R14") (pin "2") (pinfunction "2_2") (pintype "passive"))
      (node (ref "VD5") (pin "1") (pinfunction "1_1") (pintype "passive"))
    )
    (net (code "30") (name "Net-(R15-Pad2)") (class "Default")
      (node (ref "R15") (pin "2") (pinfunction "2_2") (pintype "passive"))
      (node (ref "VD6") (pin "1") (pinfunction "1_1") (pintype "passive"))
    )
    (net (code "31") (name "Net-(ST1-BYPASS)") (class "Default")
      (node (ref "C25") (pin "2") (pinfunction "2_2") (pintype "passive"))
      (node (ref "ST1") (pin "4") (pinfunction "BYPASS_4") (pintype "passive"))
    )
    (net (code "32") (name "Net-(U1-RFin)") (class "Default")
      (node (ref "C1") (pin "2") (pinfunction "2_2") (pintype "passive"))
      (node (ref "U1") (pin "1") (pinfunction "RFin_1") (pintype "passive"))
    )
    (net (code "33") (name "Net-(U1-RFout)") (class "Default")
      (node (ref "C11") (pin "1") (pinfunction "1_1") (pintype "passive"))
      (node (ref "L4") (pin "1") (pinfunction "1_1") (pintype "passive"))
      (node (ref "U1") (pin "3") (pinfunction "RFout_3") (pintype "passive"))
    )
    (net (code "34") (name "Net-(U2-INPUT)") (class "Default")
      (node (ref "C21") (pin "1") (pinfunction "1_1") (pintype "passive"))
      (node (ref "L6") (pin "2") (pinfunction "2_2") (pintype "passive"))
      (node (ref "U2") (pin "4") (pinfunction "INPUT_4") (pintype "passive"))
    )
    (net (code "35") (name "Net-(U2-OUTPUT)") (class "Default")
      (node (ref "C16") (pin "2") (pinfunction "2_2") (pintype "passive"))
      (node (ref "U2") (pin "2") (pinfunction "OUTPUT_2") (pintype "passive"))
    )
    (net (code "36") (name "Net-(U3-CTS)") (class "Default")
      (node (ref "U3") (pin "1") (pinfunction "CTS_1") (pintype "passive"))
      (node (ref "XS1") (pin "5") (pinfunction "5_5") (pintype "passive"))
    )
    (net (code "37") (name "Net-(U3-RFOUT)") (class "Default")
      (node (ref "C21") (pin "2") (pinfunction "2_2") (pintype "passive"))
      (node (ref "U3") (pin "14") (pinfunction "RFOUT_14") (pintype "passive"))
    )
    (net (code "38") (name "Net-(U3-RTS)") (class "Default")
      (node (ref "U3") (pin "2") (pinfunction "RTS_2") (pintype "passive"))
      (node (ref "XS1") (pin "6") (pinfunction "6_6") (pintype "passive"))
    )
    (net (code "39") (name "Net-(U3-RxD)") (class "Default")
      (node (ref "U3") (pin "27") (pinfunction "RxD_27") (pintype "passive"))
      (node (ref "XS1") (pin "4") (pinfunction "4_4") (pintype "passive"))
    )
    (net (code "40") (name "Net-(U3-TxD)") (class "Default")
      (node (ref "U3") (pin "26") (pinfunction "TxD_26") (pintype "passive"))
      (node (ref "XS1") (pin "3") (pinfunction "3_3") (pintype "passive"))
    )
    (net (code "41") (name "Net-(U3-VRF)") (class "Default")
      (node (ref "C20") (pin "1") (pinfunction "1_1") (pintype "passive"))
      (node (ref "C22") (pin "2") (pinfunction "2_2") (pintype "passive"))
      (node (ref "L5") (pin "2") (pinfunction "2_2") (pintype "passive"))
      (node (ref "R7") (pin "1") (pinfunction "1_1") (pintype "passive"))
      (node (ref "U3") (pin "7") (pinfunction "VRF_7") (pintype "passive"))
    )
    (net (code "42") (name "Net-(VT1-G)") (class "Default")
      (node (ref "R11") (pin "2") (pinfunction "2_2") (pintype "passive"))
      (node (ref "R8") (pin "1") (pinfunction "1_1") (pintype "passive"))
      (node (ref "VT1") (pin "1") (pinfunction "G_1") (pintype "passive"))
    )
    (net (code "43") (name "Net-(VT2-G)") (class "Default")
      (node (ref "R12") (pin "2") (pinfunction "2_2") (pintype "passive"))
      (node (ref "R9") (pin "1") (pinfunction "1_1") (pintype "passive"))
      (node (ref "VT2") (pin "1") (pinfunction "G_1") (pintype "passive"))
    )
    (net (code "44") (name "Net-(VT3-G)") (class "Default")
      (node (ref "R10") (pin "1") (pinfunction "1_1") (pintype "passive"))
      (node (ref "R13") (pin "2") (pinfunction "2_2") (pintype "passive"))
      (node (ref "VT3") (pin "1") (pinfunction "G_1") (pintype "passive"))
    )
    (net (code "45") (name "Net-(XS2-Pad6)") (class "Default")
      (node (ref "XS2") (pin "6") (pinfunction "6_6") (pintype "passive"))
      (node (ref "XS2") (pin "7") (pinfunction "7_7") (pintype "passive"))
    )
    (net (code "46") (name "unconnected-(DA1-NC-Pad5)") (class "Default")
      (node (ref "DA1") (pin "5") (pinfunction "NC_5") (pintype "passive"))
    )
    (net (code "47") (name "unconnected-(DA1-NC-Pad8)") (class "Default")
      (node (ref "DA1") (pin "8") (pinfunction "NC_8") (pintype "passive"))
    )
    (net (code "48") (name "unconnected-(L1-Pad1)") (class "Default")
      (node (ref "L1") (pin "1") (pinfunction "1_1") (pintype "passive"))
    )
    (net (code "49") (name "unconnected-(L1-Pad4)") (class "Default")
      (node (ref "L1") (pin "4") (pinfunction "4_4") (pintype "passive"))
    )
    (net (code "50") (name "unconnected-(U3-NC-Pad3)") (class "Default")
      (node (ref "U3") (pin "3") (pinfunction "NC_3") (pintype "passive+no_connect"))
    )
    (net (code "51") (name "unconnected-(U3-NC-Pad4)") (class "Default")
      (node (ref "U3") (pin "4") (pinfunction "NC_4") (pintype "passive+no_connect"))
    )
    (net (code "52") (name "unconnected-(U3-NC-Pad5)") (class "Default")
      (node (ref "U3") (pin "5") (pinfunction "NC_5") (pintype "passive+no_connect"))
    )
    (net (code "53") (name "unconnected-(U3-NC-Pad6)") (class "Default")
      (node (ref "U3") (pin "6") (pinfunction "NC_6") (pintype "passive+no_connect"))
    )
    (net (code "54") (name "unconnected-(U3-NC-Pad21)") (class "Default")
      (node (ref "U3") (pin "21") (pinfunction "NC_21") (pintype "passive+no_connect"))
    )
    (net (code "55") (name "unconnected-(U3-NC-Pad22)") (class "Default")
      (node (ref "U3") (pin "22") (pinfunction "NC_22") (pintype "passive+no_connect"))
    )
    (net (code "56") (name "unconnected-(U3-NC-Pad23)") (class "Default")
      (node (ref "U3") (pin "23") (pinfunction "NC_23") (pintype "passive+no_connect"))
    )
    (net (code "57") (name "unconnected-(U3-NC-Pad25)") (class "Default")
      (node (ref "U3") (pin "25") (pinfunction "NC_25") (pintype "passive+no_connect"))
    )
    (net (code "58") (name "unconnected-(U3-PGE-Pad30)") (class "Default")
      (node (ref "U3") (pin "30") (pinfunction "PGE_30") (pintype "passive+no_connect"))
    )
    (net (code "59") (name "unconnected-(XS1-Pad1)") (class "Default")
      (node (ref "XS1") (pin "1") (pinfunction "1_1") (pintype "passive"))
    )
  )
)
